# nrf52_linkit.net
KiCad netlist of a schematic drawn in Altium Designer
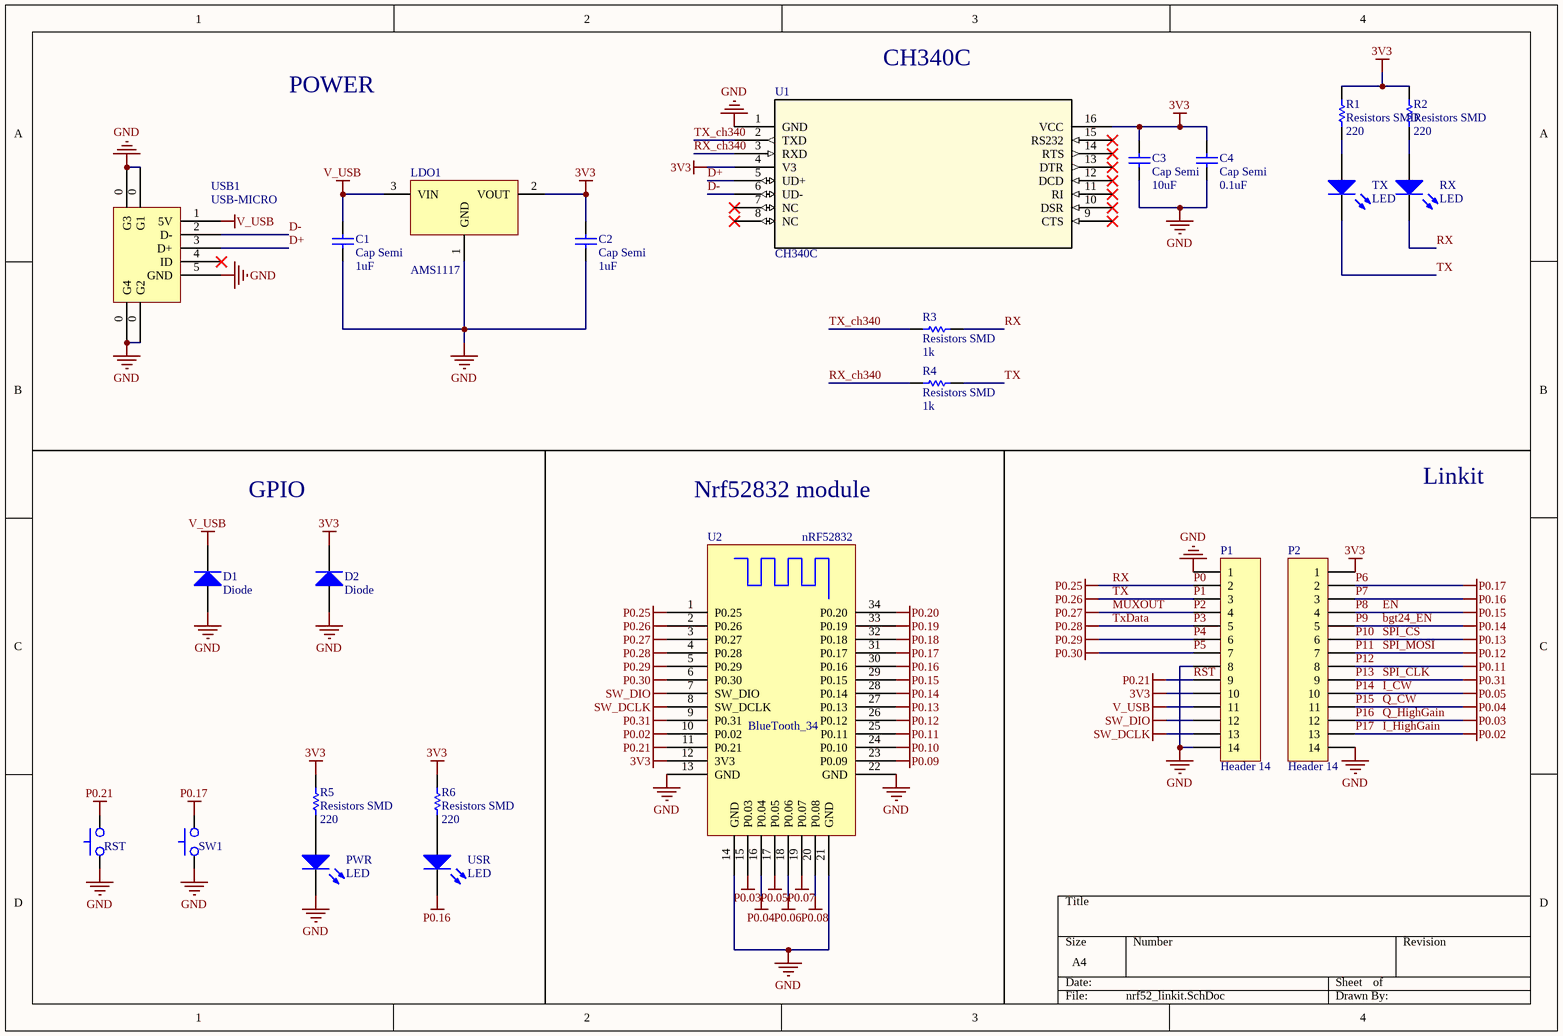
[diagram p0: nrf52_linkit.SchDoc]

(export (version "E")
  (design (tool "Eeschema 10.0.6"))
  (components
    (comp (ref "C1")
      (value "Cap Semi")
      (footprint "C0603")
      (description "Capacitor (Semiconductor SIM Model)")
      (fields (field (name "ALTIUM_VALUE") "1uF") (field (name "PUBLISHER") "Altium Limited"))
      (libsource (lib "Mylibrary") (part "Cap Semi"))
    )
    (comp (ref "C2")
      (value "Cap Semi")
      (footprint "C0603")
      (description "Capacitor (Semiconductor SIM Model)")
      (fields (field (name "ALTIUM_VALUE") "1uF") (field (name "PUBLISHER") "Altium Limited"))
      (libsource (lib "Mylibrary") (part "Cap Semi"))
    )
    (comp (ref "C3")
      (value "Cap Semi")
      (footprint "C0603")
      (description "Capacitor (Semiconductor SIM Model)")
      (fields (field (name "ALTIUM_VALUE") "10uF") (field (name "PUBLISHER") "Altium Limited"))
      (libsource (lib "Mylibrary") (part "Cap Semi"))
    )
    (comp (ref "C4")
      (value "Cap Semi")
      (footprint "C0603")
      (description "Capacitor (Semiconductor SIM Model)")
      (fields (field (name "ALTIUM_VALUE") "0.1uF") (field (name "PUBLISHER") "Altium Limited"))
      (libsource (lib "Mylibrary") (part "Cap Semi"))
    )
    (comp (ref "D1")
      (value "Diode")
      (footprint "6-0805_M")
      (description "Default Diode")
      (fields (field (name "PUBLISHER") "Altium Limited"))
      (libsource (lib "Miscellaneous Devices") (part "Diode"))
    )
    (comp (ref "D2")
      (value "Diode")
      (footprint "6-0805_M")
      (description "Default Diode")
      (fields (field (name "PUBLISHER") "Altium Limited"))
      (libsource (lib "Miscellaneous Devices") (part "Diode"))
    )
    (comp (ref "LDO1") (value "AMS1117") (footprint "SOT-223") (libsource (lib "Mylibrary") (part "AMS1117")))
    (comp (ref "P1")
      (value "Header 14")
      (footprint "HDR1X14")
      (description "Header, 14-Pin")
      (fields (field (name "PUBLISHER") "Altium Limited"))
      (libsource (lib "") (part "Header 14_1"))
    )
    (comp (ref "P2")
      (value "Header 14")
      (footprint "HDR1X14")
      (description "Header, 14-Pin")
      (fields (field (name "PUBLISHER") "Altium Limited"))
      (libsource (lib "Miscellaneous Connectors") (part "Header 14"))
    )
    (comp (ref "PWR")
      (value "LED")
      (footprint "0603")
      (description "Typical INFRARED GaAs LED")
      (fields (field (name "PUBLISHER") "Altium Limited"))
      (libsource (lib "Mylibrary") (part "LED"))
    )
    (comp (ref "R1")
      (value "Resistors SMD")
      (footprint "R0603-M")
      (description "Resistor")
      (fields (field (name "ALTIUM_VALUE") "220"))
      (libsource (lib "Mylibrary") (part "Resistors SMD"))
    )
    (comp (ref "R2")
      (value "Resistors SMD")
      (footprint "R0603-M")
      (description "Resistor")
      (fields (field (name "ALTIUM_VALUE") "220"))
      (libsource (lib "Mylibrary") (part "Resistors SMD"))
    )
    (comp (ref "R3")
      (value "Resistors SMD")
      (footprint "R0603-M")
      (description "Resistor")
      (fields (field (name "ALTIUM_VALUE") "1k"))
      (libsource (lib "Mylibrary") (part "Resistors SMD"))
    )
    (comp (ref "R4")
      (value "Resistors SMD")
      (footprint "R0603-M")
      (description "Resistor")
      (fields (field (name "ALTIUM_VALUE") "1k"))
      (libsource (lib "Mylibrary") (part "Resistors SMD"))
    )
    (comp (ref "R5")
      (value "Resistors SMD")
      (footprint "R0603-M")
      (description "Resistor")
      (fields (field (name "ALTIUM_VALUE") "220"))
      (libsource (lib "Mylibrary") (part "Resistors SMD"))
    )
    (comp (ref "R6")
      (value "Resistors SMD")
      (footprint "R0603-M")
      (description "Resistor")
      (fields (field (name "ALTIUM_VALUE") "220"))
      (libsource (lib "Mylibrary") (part "Resistors SMD"))
    )
    (comp (ref "RST")
      (value "SW-PB")
      (footprint "SWITCH_SMD_4x3_DHT-1185")
      (description "按鈕開關")
      (fields (field (name "PUBLISHER") "Altium Limited"))
      (libsource (lib "NTUST_nRF51_TAG") (part "SW-PB"))
    )
    (comp (ref "RX")
      (value "LED")
      (footprint "0603")
      (description "Typical INFRARED GaAs LED")
      (fields (field (name "PUBLISHER") "Altium Limited"))
      (libsource (lib "Mylibrary") (part "LED"))
    )
    (comp (ref "SW1")
      (value "SW-PB")
      (footprint "SWITCH_SMD_4x3_DHT-1185")
      (description "按鈕開關")
      (fields (field (name "PUBLISHER") "Altium Limited"))
      (libsource (lib "NTUST_nRF51_TAG") (part "SW-PB"))
    )
    (comp (ref "TX")
      (value "LED")
      (footprint "0603")
      (description "Typical INFRARED GaAs LED")
      (fields (field (name "PUBLISHER") "Altium Limited"))
      (libsource (lib "Mylibrary") (part "LED"))
    )
    (comp (ref "U1")
      (value "CH340C")
      (footprint "SOP16-M")
      (description "No Description Available")
      (libsource (lib "Mylibrary") (part "CH340C"))
    )
    (comp (ref "U2")
      (value "nRF52832")
      (footprint "BlueTooth_34_SMD")
      (libsource (lib "Mylibrary") (part "nRF52832"))
    )
    (comp (ref "USB1")
      (value "USB-MICRO")
      (footprint "USB-MICRO")
      (libsource (lib "Mylibrary") (part "USB-MICRO"))
    )
    (comp (ref "USR")
      (value "LED")
      (footprint "0603")
      (description "Typical INFRARED GaAs LED")
      (fields (field (name "PUBLISHER") "Altium Limited"))
      (libsource (lib "Mylibrary") (part "LED"))
    )
  )
  (nets
    (net (code "1") (name "/D+") (class "Default")
      (node (ref "U1") (pin "5") (pinfunction "UD+_5") (pintype "bidirectional"))
      (node (ref "USB1") (pin "3") (pinfunction "D+_3") (pintype "passive"))
    )
    (net (code "2") (name "/D-") (class "Default")
      (node (ref "U1") (pin "6") (pinfunction "UD-_6") (pintype "bidirectional"))
      (node (ref "USB1") (pin "2") (pinfunction "D-_2") (pintype "passive"))
    )
    (net (code "3") (name "/RX_ch340") (class "Default")
      (node (ref "R4") (pin "2") (pinfunction "2_2") (pintype "passive"))
      (node (ref "U1") (pin "3") (pinfunction "RXD_3") (pintype "input"))
    )
    (net (code "4") (name "/TX_ch340") (class "Default")
      (node (ref "R3") (pin "2") (pinfunction "2_2") (pintype "passive"))
      (node (ref "U1") (pin "2") (pinfunction "TXD_2") (pintype "output"))
    )
    (net (code "5") (name "3V3") (class "Default")
      (node (ref "C2") (pin "2") (pinfunction "2_2") (pintype "passive"))
      (node (ref "C3") (pin "2") (pinfunction "2_2") (pintype "passive"))
      (node (ref "C4") (pin "2") (pinfunction "2_2") (pintype "passive"))
      (node (ref "D2") (pin "2") (pinfunction "K_2") (pintype "passive"))
      (node (ref "LDO1") (pin "2") (pinfunction "VOUT_2") (pintype "passive"))
      (node (ref "P1") (pin "10") (pinfunction "10_10") (pintype "passive"))
      (node (ref "P2") (pin "1") (pinfunction "1_1") (pintype "passive"))
      (node (ref "R1") (pin "2") (pinfunction "2_2") (pintype "passive"))
      (node (ref "R2") (pin "2") (pinfunction "2_2") (pintype "passive"))
      (node (ref "R5") (pin "2") (pinfunction "2_2") (pintype "passive"))
      (node (ref "R6") (pin "2") (pinfunction "2_2") (pintype "passive"))
      (node (ref "U1") (pin "16") (pinfunction "VCC_16") (pintype "power_in"))
      (node (ref "U1") (pin "4") (pinfunction "V3_4") (pintype "power_in"))
      (node (ref "U2") (pin "12") (pinfunction "3V3_12") (pintype "passive"))
    )
    (net (code "6") (name "GND") (class "Default")
      (node (ref "C1") (pin "1") (pinfunction "1_1") (pintype "passive"))
      (node (ref "C2") (pin "1") (pinfunction "1_1") (pintype "passive"))
      (node (ref "C3") (pin "1") (pinfunction "1_1") (pintype "passive"))
      (node (ref "C4") (pin "1") (pinfunction "1_1") (pintype "passive"))
      (node (ref "D1") (pin "1") (pinfunction "A_1") (pintype "passive"))
      (node (ref "D2") (pin "1") (pinfunction "A_1") (pintype "passive"))
      (node (ref "LDO1") (pin "1") (pinfunction "GND_1") (pintype "passive"))
      (node (ref "P1") (pin "1") (pinfunction "1_1") (pintype "passive"))
      (node (ref "P1") (pin "14") (pinfunction "14_14") (pintype "passive"))
      (node (ref "P1") (pin "8") (pinfunction "8_8") (pintype "passive"))
      (node (ref "P2") (pin "14") (pinfunction "14_14") (pintype "passive"))
      (node (ref "PWR") (pin "2") (pinfunction "K_2") (pintype "passive"))
      (node (ref "RST") (pin "2") (pinfunction "2_2") (pintype "passive"))
      (node (ref "SW1") (pin "2") (pinfunction "2_2") (pintype "passive"))
      (node (ref "U1") (pin "1") (pinfunction "GND_1") (pintype "power_in"))
      (node (ref "U2") (pin "13") (pinfunction "GND_13") (pintype "passive"))
      (node (ref "U2") (pin "14") (pinfunction "GND_14") (pintype "passive"))
      (node (ref "U2") (pin "21") (pinfunction "GND_21") (pintype "passive"))
      (node (ref "U2") (pin "22") (pinfunction "GND_22") (pintype "passive"))
      (node (ref "USB1") (pin "0") (pinfunction "G2_0") (pintype "power_in"))
      (node (ref "USB1") (pin "5") (pinfunction "GND_5") (pintype "passive"))
    )
    (net (code "7") (name "Net-(PWR-A)") (class "Default")
      (node (ref "PWR") (pin "1") (pinfunction "A_1") (pintype "passive"))
      (node (ref "R5") (pin "1") (pinfunction "1_1") (pintype "passive"))
    )
    (net (code "8") (name "Net-(RX-A)") (class "Default")
      (node (ref "R2") (pin "1") (pinfunction "1_1") (pintype "passive"))
      (node (ref "RX") (pin "1") (pinfunction "A_1") (pintype "passive"))
    )
    (net (code "9") (name "Net-(TX-A)") (class "Default")
      (node (ref "R1") (pin "1") (pinfunction "1_1") (pintype "passive"))
      (node (ref "TX") (pin "1") (pinfunction "A_1") (pintype "passive"))
    )
    (net (code "10") (name "Net-(USR-A)") (class "Default")
      (node (ref "R6") (pin "1") (pinfunction "1_1") (pintype "passive"))
      (node (ref "USR") (pin "1") (pinfunction "A_1") (pintype "passive"))
    )
    (net (code "11") (name "P0.02") (class "Default")
      (node (ref "P2") (pin "13") (pinfunction "13_13") (pintype "passive"))
      (node (ref "U2") (pin "10") (pinfunction "P0.02_10") (pintype "passive"))
    )
    (net (code "12") (name "P0.03") (class "Default")
      (node (ref "P2") (pin "12") (pinfunction "12_12") (pintype "passive"))
      (node (ref "U2") (pin "15") (pinfunction "P0.03_15") (pintype "passive"))
    )
    (net (code "13") (name "P0.04") (class "Default")
      (node (ref "P2") (pin "11") (pinfunction "11_11") (pintype "passive"))
      (node (ref "U2") (pin "16") (pinfunction "P0.04_16") (pintype "passive"))
    )
    (net (code "14") (name "P0.05") (class "Default")
      (node (ref "P2") (pin "10") (pinfunction "10_10") (pintype "passive"))
      (node (ref "U2") (pin "17") (pinfunction "P0.05_17") (pintype "passive"))
    )
    (net (code "15") (name "P0.06") (class "Default")
      (node (ref "U2") (pin "18") (pinfunction "P0.06_18") (pintype "passive"))
    )
    (net (code "16") (name "P0.07") (class "Default")
      (node (ref "U2") (pin "19") (pinfunction "P0.07_19") (pintype "passive"))
    )
    (net (code "17") (name "P0.08") (class "Default")
      (node (ref "U2") (pin "20") (pinfunction "P0.08_20") (pintype "passive"))
    )
    (net (code "18") (name "P0.09") (class "Default")
      (node (ref "U2") (pin "23") (pinfunction "P0.09_23") (pintype "passive"))
    )
    (net (code "19") (name "P0.10") (class "Default")
      (node (ref "U2") (pin "24") (pinfunction "P0.10_24") (pintype "passive"))
    )
    (net (code "20") (name "P0.11") (class "Default")
      (node (ref "P2") (pin "8") (pinfunction "8_8") (pintype "passive"))
      (node (ref "U2") (pin "25") (pinfunction "P0.11_25") (pintype "passive"))
    )
    (net (code "21") (name "P0.12") (class "Default")
      (node (ref "P2") (pin "7") (pinfunction "7_7") (pintype "passive"))
      (node (ref "U2") (pin "26") (pinfunction "P0.12_26") (pintype "passive"))
    )
    (net (code "22") (name "P0.13") (class "Default")
      (node (ref "P2") (pin "6") (pinfunction "6_6") (pintype "passive"))
      (node (ref "U2") (pin "27") (pinfunction "P0.13_27") (pintype "passive"))
    )
    (net (code "23") (name "P0.14") (class "Default")
      (node (ref "P2") (pin "5") (pinfunction "5_5") (pintype "passive"))
      (node (ref "U2") (pin "28") (pinfunction "P0.14_28") (pintype "passive"))
    )
    (net (code "24") (name "P0.15") (class "Default")
      (node (ref "P2") (pin "4") (pinfunction "4_4") (pintype "passive"))
      (node (ref "U2") (pin "29") (pinfunction "P0.15_29") (pintype "passive"))
    )
    (net (code "25") (name "P0.16") (class "Default")
      (node (ref "P2") (pin "3") (pinfunction "3_3") (pintype "passive"))
      (node (ref "U2") (pin "30") (pinfunction "P0.16_30") (pintype "passive"))
      (node (ref "USR") (pin "2") (pinfunction "K_2") (pintype "passive"))
    )
    (net (code "26") (name "P0.17") (class "Default")
      (node (ref "P2") (pin "2") (pinfunction "2_2") (pintype "passive"))
      (node (ref "SW1") (pin "1") (pinfunction "1_1") (pintype "passive"))
      (node (ref "U2") (pin "31") (pinfunction "P0.17_31") (pintype "passive"))
    )
    (net (code "27") (name "P0.18") (class "Default")
      (node (ref "U2") (pin "32") (pinfunction "P0.18_32") (pintype "passive"))
    )
    (net (code "28") (name "P0.19") (class "Default")
      (node (ref "U2") (pin "33") (pinfunction "P0.19_33") (pintype "passive"))
    )
    (net (code "29") (name "P0.20") (class "Default")
      (node (ref "U2") (pin "34") (pinfunction "P0.20_34") (pintype "passive"))
    )
    (net (code "30") (name "P0.21") (class "Default")
      (node (ref "P1") (pin "9") (pinfunction "9_9") (pintype "passive"))
      (node (ref "RST") (pin "1") (pinfunction "1_1") (pintype "passive"))
      (node (ref "U2") (pin "11") (pinfunction "P0.21_11") (pintype "passive"))
    )
    (net (code "31") (name "P0.25") (class "Default")
      (node (ref "P1") (pin "2") (pinfunction "2_2") (pintype "passive"))
      (node (ref "R3") (pin "1") (pinfunction "1_1") (pintype "passive"))
      (node (ref "RX") (pin "2") (pinfunction "K_2") (pintype "passive"))
      (node (ref "U2") (pin "1") (pinfunction "P0.25_1") (pintype "passive"))
    )
    (net (code "32") (name "P0.26") (class "Default")
      (node (ref "P1") (pin "3") (pinfunction "3_3") (pintype "passive"))
      (node (ref "R4") (pin "1") (pinfunction "1_1") (pintype "passive"))
      (node (ref "TX") (pin "2") (pinfunction "K_2") (pintype "passive"))
      (node (ref "U2") (pin "2") (pinfunction "P0.26_2") (pintype "passive"))
    )
    (net (code "33") (name "P0.27") (class "Default")
      (node (ref "P1") (pin "4") (pinfunction "4_4") (pintype "passive"))
      (node (ref "U2") (pin "3") (pinfunction "P0.27_3") (pintype "passive"))
    )
    (net (code "34") (name "P0.28") (class "Default")
      (node (ref "P1") (pin "5") (pinfunction "5_5") (pintype "passive"))
      (node (ref "U2") (pin "4") (pinfunction "P0.28_4") (pintype "passive"))
    )
    (net (code "35") (name "P0.29") (class "Default")
      (node (ref "P1") (pin "6") (pinfunction "6_6") (pintype "passive"))
      (node (ref "U2") (pin "5") (pinfunction "P0.29_5") (pintype "passive"))
    )
    (net (code "36") (name "P0.30") (class "Default")
      (node (ref "P1") (pin "7") (pinfunction "7_7") (pintype "passive"))
      (node (ref "U2") (pin "6") (pinfunction "P0.30_6") (pintype "passive"))
    )
    (net (code "37") (name "P0.31") (class "Default")
      (node (ref "P2") (pin "9") (pinfunction "9_9") (pintype "passive"))
      (node (ref "U2") (pin "9") (pinfunction "P0.31_9") (pintype "passive"))
    )
    (net (code "38") (name "SW_DCLK") (class "Default")
      (node (ref "P1") (pin "13") (pinfunction "13_13") (pintype "passive"))
      (node (ref "U2") (pin "8") (pinfunction "SW_DCLK_8") (pintype "passive"))
    )
    (net (code "39") (name "SW_DIO") (class "Default")
      (node (ref "P1") (pin "12") (pinfunction "12_12") (pintype "passive"))
      (node (ref "U2") (pin "7") (pinfunction "SW_DIO_7") (pintype "passive"))
    )
    (net (code "40") (name "V_USB") (class "Default")
      (node (ref "C1") (pin "2") (pinfunction "2_2") (pintype "passive"))
      (node (ref "D1") (pin "2") (pinfunction "K_2") (pintype "passive"))
      (node (ref "LDO1") (pin "3") (pinfunction "VIN_3") (pintype "passive"))
      (node (ref "P1") (pin "11") (pinfunction "11_11") (pintype "passive"))
      (node (ref "USB1") (pin "1") (pinfunction "5V_1") (pintype "passive"))
    )
    (net (code "41") (name "unconnected-(U1-CTS-Pad9)") (class "Default")
      (node (ref "U1") (pin "9") (pinfunction "CTS_9") (pintype "input+no_connect"))
    )
    (net (code "42") (name "unconnected-(U1-DCD-Pad12)") (class "Default")
      (node (ref "U1") (pin "12") (pinfunction "DCD_12") (pintype "input+no_connect"))
    )
    (net (code "43") (name "unconnected-(U1-DSR-Pad10)") (class "Default")
      (node (ref "U1") (pin "10") (pinfunction "DSR_10") (pintype "input+no_connect"))
    )
    (net (code "44") (name "unconnected-(U1-DTR-Pad13)") (class "Default")
      (node (ref "U1") (pin "13") (pinfunction "DTR_13") (pintype "output+no_connect"))
    )
    (net (code "45") (name "unconnected-(U1-NC-Pad7)") (class "Default")
      (node (ref "U1") (pin "7") (pinfunction "NC_7") (pintype "bidirectional+no_connect"))
    )
    (net (code "46") (name "unconnected-(U1-NC-Pad8)") (class "Default")
      (node (ref "U1") (pin "8") (pinfunction "NC_8") (pintype "bidirectional+no_connect"))
    )
    (net (code "47") (name "unconnected-(U1-RI-Pad11)") (class "Default")
      (node (ref "U1") (pin "11") (pinfunction "RI_11") (pintype "input+no_connect"))
    )
    (net (code "48") (name "unconnected-(U1-RS232-Pad15)") (class "Default")
      (node (ref "U1") (pin "15") (pinfunction "RS232_15") (pintype "input+no_connect"))
    )
    (net (code "49") (name "unconnected-(U1-RTS-Pad14)") (class "Default")
      (node (ref "U1") (pin "14") (pinfunction "RTS_14") (pintype "output+no_connect"))
    )
    (net (code "50") (name "unconnected-(USB1-ID-Pad4)") (class "Default")
      (node (ref "USB1") (pin "4") (pinfunction "ID_4") (pintype "passive+no_connect"))
    )
  )
)
